# Sine_5KW_co_sac.net
KiCad netlist of a schematic drawn in EAGLE
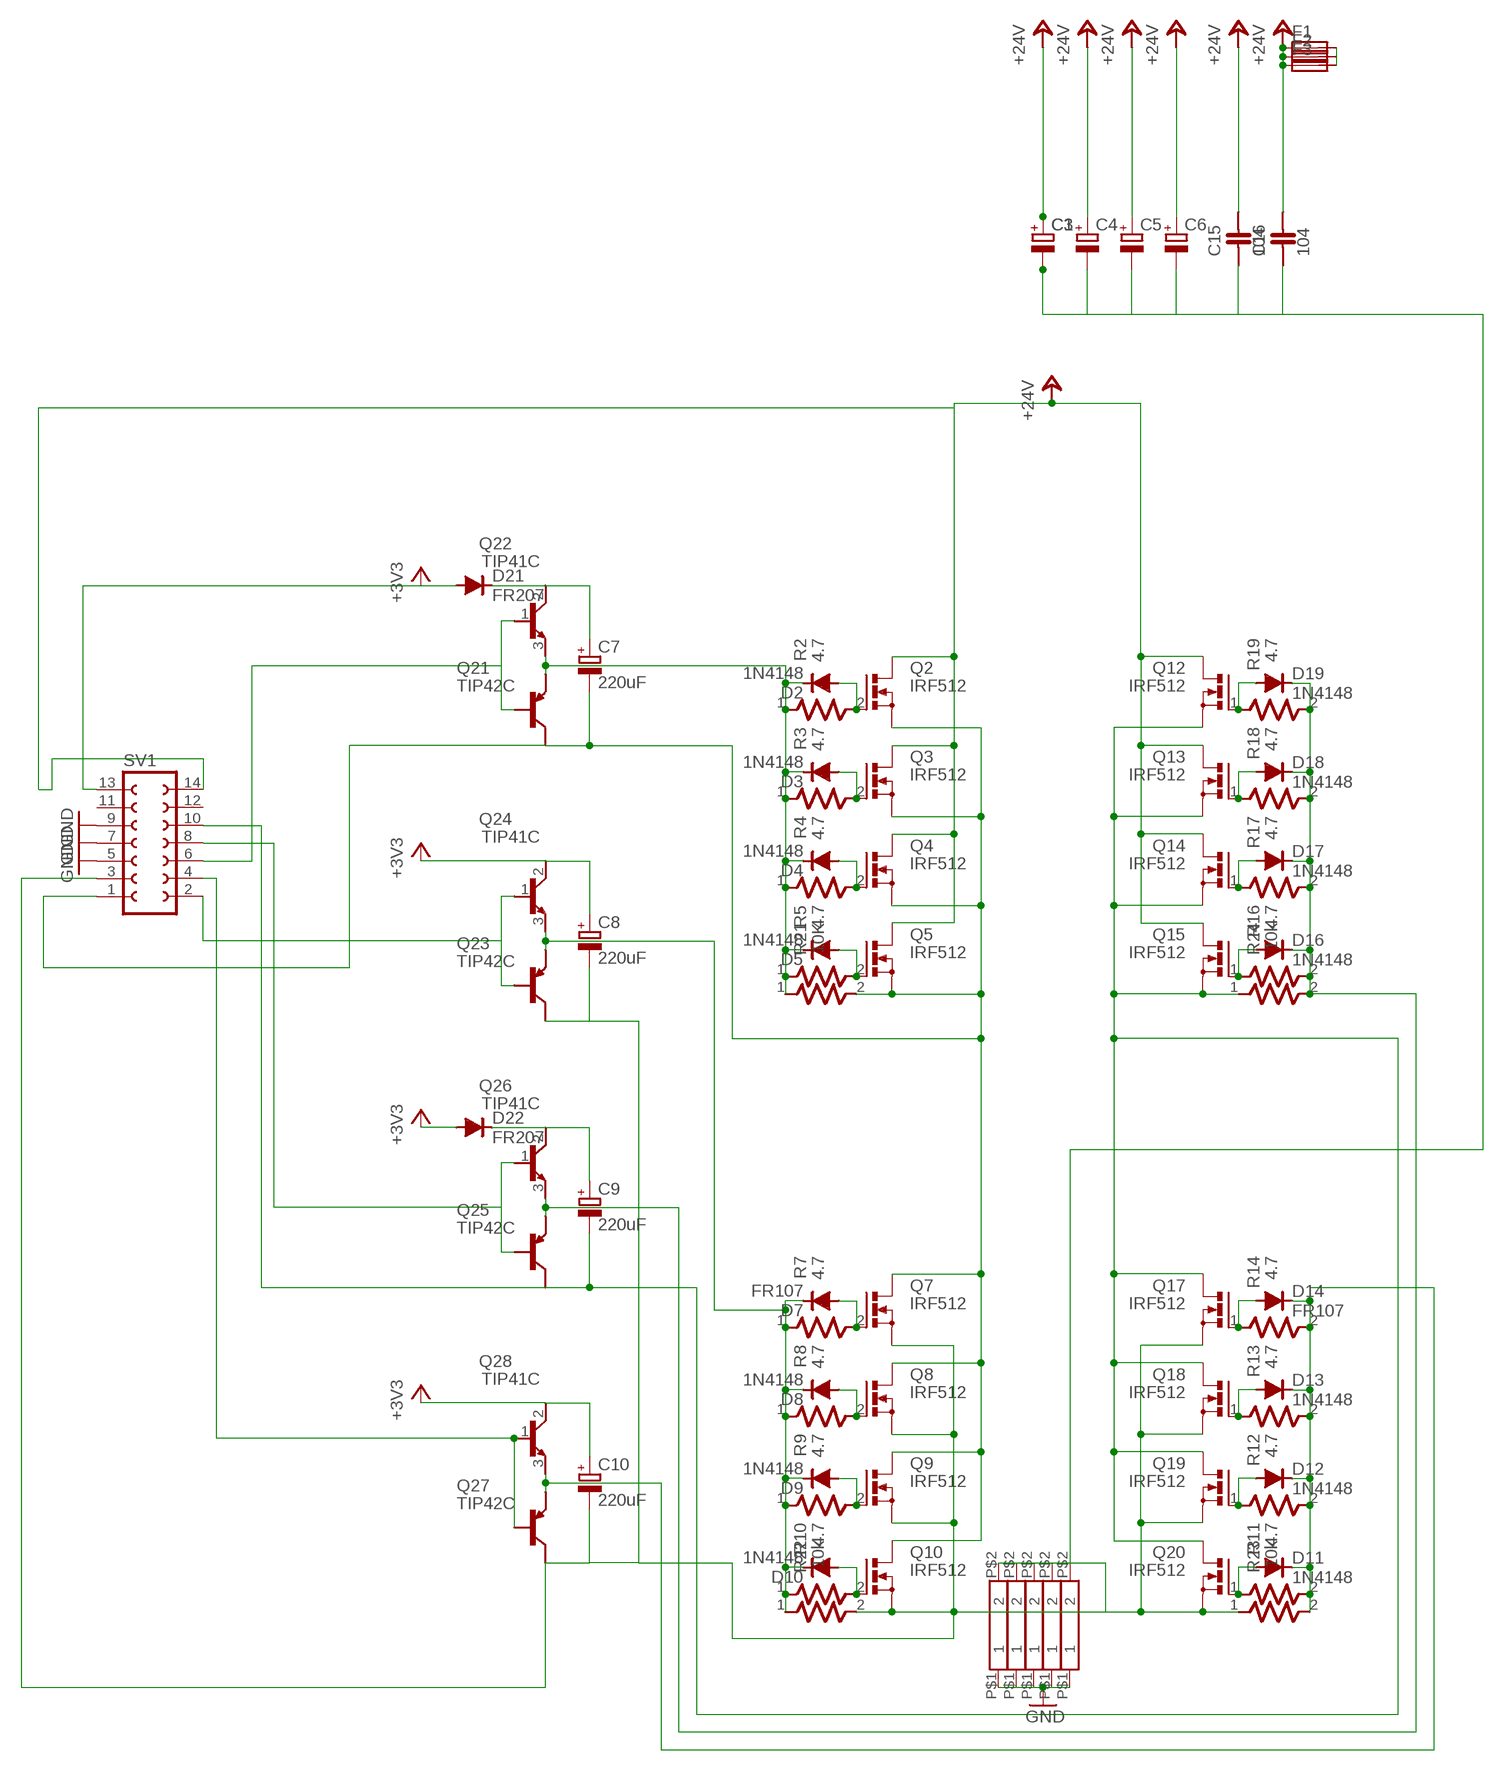
[diagram p0: schematic, sheet 1]

(export (version "E")
  (design (tool "Eeschema 10.0.6"))
  (components
    (comp (ref "C1")
      (value "CPOL-EUE7.5-18")
      (footprint "eagle-import:E7,5-18")
      (libsource (lib "eagle-import") (part "CPOL-EUE7.5-18"))
    )
    (comp (ref "C3")
      (value "CPOL-EUE7.5-18")
      (footprint "eagle-import:E7,5-18")
      (libsource (lib "eagle-import") (part "CPOL-EUE7.5-18"))
    )
    (comp (ref "C4")
      (value "CPOL-EUE7.5-18")
      (footprint "eagle-import:E7,5-18")
      (libsource (lib "eagle-import") (part "CPOL-EUE7.5-18"))
    )
    (comp (ref "C5")
      (value "CPOL-EUE7.5-18")
      (footprint "eagle-import:E7,5-18")
      (libsource (lib "eagle-import") (part "CPOL-EUE7.5-18"))
    )
    (comp (ref "C6")
      (value "CPOL-EUE7.5-18")
      (footprint "eagle-import:E7,5-18")
      (libsource (lib "eagle-import") (part "CPOL-EUE7.5-18"))
    )
    (comp (ref "C7")
      (value "220uF")
      (footprint "eagle-import:E5-8,5")
      (libsource (lib "eagle-import") (part "CPOL-EUE5-8.5"))
    )
    (comp (ref "C8")
      (value "220uF")
      (footprint "eagle-import:E5-8,5")
      (libsource (lib "eagle-import") (part "CPOL-EUE5-8.5"))
    )
    (comp (ref "C9")
      (value "220uF")
      (footprint "eagle-import:E5-8,5")
      (libsource (lib "eagle-import") (part "CPOL-EUE5-8.5"))
    )
    (comp (ref "C10")
      (value "220uF")
      (footprint "eagle-import:E5-8,5")
      (libsource (lib "eagle-import") (part "CPOL-EUE5-8.5"))
    )
    (comp (ref "C15")
      (value "104")
      (footprint "eagle-import:CAP-NP5")
      (libsource (lib "eagle-import") (part "CAP-NP5"))
    )
    (comp (ref "C16")
      (value "104")
      (footprint "eagle-import:CAP-NP5")
      (libsource (lib "eagle-import") (part "CAP-NP5"))
    )
    (comp (ref "D2")
      (value "1N4148")
      (footprint "eagle-import:D-7,5")
      (libsource (lib "eagle-import") (part "1N4148"))
    )
    (comp (ref "D3")
      (value "1N4148")
      (footprint "eagle-import:D-7,5")
      (libsource (lib "eagle-import") (part "1N4148"))
    )
    (comp (ref "D4")
      (value "1N4148")
      (footprint "eagle-import:D-7,5")
      (libsource (lib "eagle-import") (part "1N4148"))
    )
    (comp (ref "D5")
      (value "1N4148")
      (footprint "eagle-import:D-7,5")
      (libsource (lib "eagle-import") (part "1N4148"))
    )
    (comp (ref "D7")
      (value "FR107")
      (footprint "eagle-import:D-7,5")
      (libsource (lib "eagle-import") (part "1N4148"))
    )
    (comp (ref "D8")
      (value "1N4148")
      (footprint "eagle-import:D-7,5")
      (libsource (lib "eagle-import") (part "1N4148"))
    )
    (comp (ref "D9")
      (value "1N4148")
      (footprint "eagle-import:D-7,5")
      (libsource (lib "eagle-import") (part "1N4148"))
    )
    (comp (ref "D10")
      (value "1N4148")
      (footprint "eagle-import:D-7,5")
      (libsource (lib "eagle-import") (part "1N4148"))
    )
    (comp (ref "D11")
      (value "1N4148")
      (footprint "eagle-import:D-7,5")
      (libsource (lib "eagle-import") (part "1N4148"))
    )
    (comp (ref "D12")
      (value "1N4148")
      (footprint "eagle-import:D-7,5")
      (libsource (lib "eagle-import") (part "1N4148"))
    )
    (comp (ref "D13")
      (value "1N4148")
      (footprint "eagle-import:D-7,5")
      (libsource (lib "eagle-import") (part "1N4148"))
    )
    (comp (ref "D14")
      (value "FR107")
      (footprint "eagle-import:D-7,5")
      (libsource (lib "eagle-import") (part "1N4148"))
    )
    (comp (ref "D16")
      (value "1N4148")
      (footprint "eagle-import:D-7,5")
      (libsource (lib "eagle-import") (part "1N4148"))
    )
    (comp (ref "D17")
      (value "1N4148")
      (footprint "eagle-import:D-7,5")
      (libsource (lib "eagle-import") (part "1N4148"))
    )
    (comp (ref "D18")
      (value "1N4148")
      (footprint "eagle-import:D-7,5")
      (libsource (lib "eagle-import") (part "1N4148"))
    )
    (comp (ref "D19")
      (value "1N4148")
      (footprint "eagle-import:D-7,5")
      (libsource (lib "eagle-import") (part "1N4148"))
    )
    (comp (ref "D21")
      (value "FR207")
      (footprint "eagle-import:D-7,5")
      (libsource (lib "eagle-import") (part "1N4148"))
    )
    (comp (ref "D22")
      (value "FR207")
      (footprint "eagle-import:D-7,5")
      (libsource (lib "eagle-import") (part "1N4148"))
    )
    (comp (ref "F1")
      (value "LITTLEFUSE")
      (footprint "eagle-import:LITTLEFUSE")
      (libsource (lib "eagle-import") (part "LITTLEFUSE"))
    )
    (comp (ref "F2")
      (value "LITTLEFUSE")
      (footprint "eagle-import:LITTLEFUSE")
      (libsource (lib "eagle-import") (part "LITTLEFUSE"))
    )
    (comp (ref "F3")
      (value "LITTLEFUSE")
      (footprint "eagle-import:LITTLEFUSE")
      (libsource (lib "eagle-import") (part "LITTLEFUSE"))
    )
    (comp (ref "Q2")
      (value "IRF512")
      (footprint "eagle-import:TO220BV")
      (libsource (lib "eagle-import") (part "IRF512"))
    )
    (comp (ref "Q3")
      (value "IRF512")
      (footprint "eagle-import:TO220BV")
      (libsource (lib "eagle-import") (part "IRF512"))
    )
    (comp (ref "Q4")
      (value "IRF512")
      (footprint "eagle-import:TO220BV")
      (libsource (lib "eagle-import") (part "IRF512"))
    )
    (comp (ref "Q5")
      (value "IRF512")
      (footprint "eagle-import:TO220BV")
      (libsource (lib "eagle-import") (part "IRF512"))
    )
    (comp (ref "Q7")
      (value "IRF512")
      (footprint "eagle-import:TO220BV")
      (libsource (lib "eagle-import") (part "IRF512"))
    )
    (comp (ref "Q8")
      (value "IRF512")
      (footprint "eagle-import:TO220BV")
      (libsource (lib "eagle-import") (part "IRF512"))
    )
    (comp (ref "Q9")
      (value "IRF512")
      (footprint "eagle-import:TO220BV")
      (libsource (lib "eagle-import") (part "IRF512"))
    )
    (comp (ref "Q10")
      (value "IRF512")
      (footprint "eagle-import:TO220BV")
      (libsource (lib "eagle-import") (part "IRF512"))
    )
    (comp (ref "Q12")
      (value "IRF512")
      (footprint "eagle-import:TO220BV")
      (libsource (lib "eagle-import") (part "IRF512"))
    )
    (comp (ref "Q13")
      (value "IRF512")
      (footprint "eagle-import:TO220BV")
      (libsource (lib "eagle-import") (part "IRF512"))
    )
    (comp (ref "Q14")
      (value "IRF512")
      (footprint "eagle-import:TO220BV")
      (fields (field (name "SPICEPREFIX") "M"))
      (libsource (lib "eagle-import") (part "IRF512"))
    )
    (comp (ref "Q15")
      (value "IRF512")
      (footprint "eagle-import:TO220BV")
      (libsource (lib "eagle-import") (part "IRF512"))
    )
    (comp (ref "Q17")
      (value "IRF512")
      (footprint "eagle-import:TO220BV")
      (libsource (lib "eagle-import") (part "IRF512"))
    )
    (comp (ref "Q18")
      (value "IRF512")
      (footprint "eagle-import:TO220BV")
      (libsource (lib "eagle-import") (part "IRF512"))
    )
    (comp (ref "Q19")
      (value "IRF512")
      (footprint "eagle-import:TO220BV")
      (libsource (lib "eagle-import") (part "IRF512"))
    )
    (comp (ref "Q20")
      (value "IRF512")
      (footprint "eagle-import:TO220BV")
      (libsource (lib "eagle-import") (part "IRF512"))
    )
    (comp (ref "Q21")
      (value "TIP42C")
      (footprint "eagle-import:TIP-127")
      (libsource (lib "eagle-import") (part "TIP-127"))
    )
    (comp (ref "Q22")
      (value "TIP41C")
      (footprint "eagle-import:TIP-127")
      (libsource (lib "eagle-import") (part "TIP122"))
    )
    (comp (ref "Q23")
      (value "TIP42C")
      (footprint "eagle-import:TIP-127")
      (libsource (lib "eagle-import") (part "TIP-127"))
    )
    (comp (ref "Q24")
      (value "TIP41C")
      (footprint "eagle-import:TIP-127")
      (libsource (lib "eagle-import") (part "TIP122"))
    )
    (comp (ref "Q25")
      (value "TIP42C")
      (footprint "eagle-import:TIP-127")
      (libsource (lib "eagle-import") (part "TIP-127"))
    )
    (comp (ref "Q26")
      (value "TIP41C")
      (footprint "eagle-import:TIP-127")
      (libsource (lib "eagle-import") (part "TIP122"))
    )
    (comp (ref "Q27")
      (value "TIP42C")
      (footprint "eagle-import:TIP-127")
      (libsource (lib "eagle-import") (part "TIP-127"))
    )
    (comp (ref "Q28")
      (value "TIP41C")
      (footprint "eagle-import:TIP-127")
      (libsource (lib "eagle-import") (part "TIP122"))
    )
    (comp (ref "R2")
      (value "4.7")
      (footprint "eagle-import:R-7,5")
      (libsource (lib "eagle-import") (part "R-7,5"))
    )
    (comp (ref "R3")
      (value "4.7")
      (footprint "eagle-import:R-7,5")
      (libsource (lib "eagle-import") (part "R-7,5"))
    )
    (comp (ref "R4")
      (value "4.7")
      (footprint "eagle-import:R-7,5")
      (libsource (lib "eagle-import") (part "R-7,5"))
    )
    (comp (ref "R5")
      (value "4.7")
      (footprint "eagle-import:R-7,5")
      (libsource (lib "eagle-import") (part "R-7,5"))
    )
    (comp (ref "R7")
      (value "4.7")
      (footprint "eagle-import:R-7,5")
      (libsource (lib "eagle-import") (part "R-7,5"))
    )
    (comp (ref "R8")
      (value "4.7")
      (footprint "eagle-import:R-7,5")
      (libsource (lib "eagle-import") (part "R-7,5"))
    )
    (comp (ref "R9")
      (value "4.7")
      (footprint "eagle-import:R-7,5")
      (libsource (lib "eagle-import") (part "R-7,5"))
    )
    (comp (ref "R10")
      (value "4.7")
      (footprint "eagle-import:R-7,5")
      (libsource (lib "eagle-import") (part "R-7,5"))
    )
    (comp (ref "R11")
      (value "4.7")
      (footprint "eagle-import:R-7,5")
      (libsource (lib "eagle-import") (part "R-7,5"))
    )
    (comp (ref "R12")
      (value "4.7")
      (footprint "eagle-import:R-7,5")
      (libsource (lib "eagle-import") (part "R-7,5"))
    )
    (comp (ref "R13")
      (value "4.7")
      (footprint "eagle-import:R-7,5")
      (libsource (lib "eagle-import") (part "R-7,5"))
    )
    (comp (ref "R14")
      (value "4.7")
      (footprint "eagle-import:R-7,5")
      (libsource (lib "eagle-import") (part "R-7,5"))
    )
    (comp (ref "R16")
      (value "4.7")
      (footprint "eagle-import:R-7,5")
      (libsource (lib "eagle-import") (part "R-7,5"))
    )
    (comp (ref "R17")
      (value "4.7")
      (footprint "eagle-import:R-7,5")
      (libsource (lib "eagle-import") (part "R-7,5"))
    )
    (comp (ref "R18")
      (value "4.7")
      (footprint "eagle-import:R-7,5")
      (libsource (lib "eagle-import") (part "R-7,5"))
    )
    (comp (ref "R19")
      (value "4.7")
      (footprint "eagle-import:R-7,5")
      (libsource (lib "eagle-import") (part "R-7,5"))
    )
    (comp (ref "R21")
      (value "10K")
      (footprint "eagle-import:R-7,5")
      (libsource (lib "eagle-import") (part "R-7,5"))
    )
    (comp (ref "R22")
      (value "10k")
      (footprint "eagle-import:R-7,5")
      (libsource (lib "eagle-import") (part "R-7,5"))
    )
    (comp (ref "R23")
      (value "10k")
      (footprint "eagle-import:R-7,5")
      (libsource (lib "eagle-import") (part "R-7,5"))
    )
    (comp (ref "R24")
      (value "10k")
      (footprint "eagle-import:R-7,5")
      (libsource (lib "eagle-import") (part "R-7,5"))
    )
    (comp (ref "SV1")
      (value "FE07-2")
      (footprint "eagle-import:FE07-2")
      (fields (field (name "SPICEPREFIX") "X"))
      (libsource (lib "eagle-import") (part "FE07-2"))
    )
    (comp (ref "U$2")
      (value "SHUNT")
      (footprint "eagle-import:SHUNT")
      (libsource (lib "eagle-import") (part "SHUNT"))
    )
    (comp (ref "U$3")
      (value "SHUNT")
      (footprint "eagle-import:SHUNT")
      (libsource (lib "eagle-import") (part "SHUNT"))
    )
    (comp (ref "U$8")
      (value "SHUNT")
      (footprint "eagle-import:SHUNT")
      (libsource (lib "eagle-import") (part "SHUNT"))
    )
    (comp (ref "U$9")
      (value "SHUNT")
      (footprint "eagle-import:SHUNT")
      (libsource (lib "eagle-import") (part "SHUNT"))
    )
    (comp (ref "U$10")
      (value "SHUNT")
      (footprint "eagle-import:SHUNT")
      (libsource (lib "eagle-import") (part "SHUNT"))
    )
  )
  (nets
    (net (code "1") (name "+3V3") (class "Default")
      (node (ref "C10") (pin "+") (pinfunction "+_+") (pintype "passive"))
      (node (ref "C8") (pin "+") (pinfunction "+_+") (pintype "passive"))
      (node (ref "D21") (pin "A") (pinfunction "A_A") (pintype "passive"))
      (node (ref "D22") (pin "A") (pinfunction "A_A") (pintype "passive"))
      (node (ref "Q24") (pin "2") (pinfunction "C_2") (pintype "passive"))
      (node (ref "Q28") (pin "2") (pinfunction "C_2") (pintype "passive"))
      (node (ref "SV1") (pin "13") (pinfunction "13_13") (pintype "passive"))
    )
    (net (code "2") (name "+24V") (class "Default")
      (node (ref "C1") (pin "+") (pinfunction "+_+") (pintype "passive"))
      (node (ref "C15") (pin "2") (pinfunction "2_2") (pintype "passive"))
      (node (ref "C16") (pin "2") (pinfunction "2_2") (pintype "passive"))
      (node (ref "C3") (pin "+") (pinfunction "+_+") (pintype "passive"))
      (node (ref "C4") (pin "+") (pinfunction "+_+") (pintype "passive"))
      (node (ref "C5") (pin "+") (pinfunction "+_+") (pintype "passive"))
      (node (ref "C6") (pin "+") (pinfunction "+_+") (pintype "passive"))
      (node (ref "F1") (pin "1") (pinfunction "1_1") (pintype "passive"))
      (node (ref "F2") (pin "1") (pinfunction "1_1") (pintype "passive"))
      (node (ref "F3") (pin "1") (pinfunction "1_1") (pintype "passive"))
      (node (ref "Q12") (pin "D") (pinfunction "D_D") (pintype "passive"))
      (node (ref "Q13") (pin "D") (pinfunction "D_D") (pintype "passive"))
      (node (ref "Q14") (pin "D") (pinfunction "D_D") (pintype "passive"))
      (node (ref "Q15") (pin "D") (pinfunction "D_D") (pintype "passive"))
      (node (ref "Q2") (pin "D") (pinfunction "D_D") (pintype "passive"))
      (node (ref "Q3") (pin "D") (pinfunction "D_D") (pintype "passive"))
      (node (ref "Q4") (pin "D") (pinfunction "D_D") (pintype "passive"))
      (node (ref "Q5") (pin "D") (pinfunction "D_D") (pintype "passive"))
      (node (ref "SV1") (pin "14") (pinfunction "14_14") (pintype "passive"))
    )
    (net (code "3") (name "GND") (class "Default")
      (node (ref "SV1") (pin "5") (pinfunction "5_5") (pintype "passive"))
      (node (ref "SV1") (pin "7") (pinfunction "7_7") (pintype "passive"))
      (node (ref "SV1") (pin "9") (pinfunction "9_9") (pintype "passive"))
      (node (ref "U$10") (pin "P$1") (pinfunction "1_P$1") (pintype "bidirectional"))
      (node (ref "U$2") (pin "P$1") (pinfunction "1_P$1") (pintype "bidirectional"))
      (node (ref "U$3") (pin "P$1") (pinfunction "1_P$1") (pintype "bidirectional"))
      (node (ref "U$8") (pin "P$1") (pinfunction "1_P$1") (pintype "bidirectional"))
      (node (ref "U$9") (pin "P$1") (pinfunction "1_P$1") (pintype "bidirectional"))
    )
    (net (code "4") (name "Net-(D2-PadA)") (class "Default")
      (node (ref "D2") (pin "A") (pinfunction "A_A") (pintype "passive"))
      (node (ref "Q2") (pin "G") (pinfunction "G_G") (pintype "passive"))
      (node (ref "R2") (pin "2") (pinfunction "2_2") (pintype "passive"))
    )
    (net (code "5") (name "Net-(D3-PadA)") (class "Default")
      (node (ref "D3") (pin "A") (pinfunction "A_A") (pintype "passive"))
      (node (ref "Q3") (pin "G") (pinfunction "G_G") (pintype "passive"))
      (node (ref "R3") (pin "2") (pinfunction "2_2") (pintype "passive"))
    )
    (net (code "6") (name "Net-(D4-PadA)") (class "Default")
      (node (ref "D4") (pin "A") (pinfunction "A_A") (pintype "passive"))
      (node (ref "Q4") (pin "G") (pinfunction "G_G") (pintype "passive"))
      (node (ref "R4") (pin "2") (pinfunction "2_2") (pintype "passive"))
    )
    (net (code "7") (name "Net-(D5-PadA)") (class "Default")
      (node (ref "D5") (pin "A") (pinfunction "A_A") (pintype "passive"))
      (node (ref "Q5") (pin "G") (pinfunction "G_G") (pintype "passive"))
      (node (ref "R5") (pin "2") (pinfunction "2_2") (pintype "passive"))
    )
    (net (code "8") (name "Net-(D7-PadA)") (class "Default")
      (node (ref "D7") (pin "A") (pinfunction "A_A") (pintype "passive"))
      (node (ref "Q7") (pin "G") (pinfunction "G_G") (pintype "passive"))
      (node (ref "R7") (pin "2") (pinfunction "2_2") (pintype "passive"))
    )
    (net (code "9") (name "Net-(D8-PadA)") (class "Default")
      (node (ref "D8") (pin "A") (pinfunction "A_A") (pintype "passive"))
      (node (ref "Q8") (pin "G") (pinfunction "G_G") (pintype "passive"))
      (node (ref "R8") (pin "2") (pinfunction "2_2") (pintype "passive"))
    )
    (net (code "10") (name "Net-(D9-PadA)") (class "Default")
      (node (ref "D9") (pin "A") (pinfunction "A_A") (pintype "passive"))
      (node (ref "Q9") (pin "G") (pinfunction "G_G") (pintype "passive"))
      (node (ref "R9") (pin "2") (pinfunction "2_2") (pintype "passive"))
    )
    (net (code "11") (name "Net-(D10-PadA)") (class "Default")
      (node (ref "D10") (pin "A") (pinfunction "A_A") (pintype "passive"))
      (node (ref "Q10") (pin "G") (pinfunction "G_G") (pintype "passive"))
      (node (ref "R10") (pin "2") (pinfunction "2_2") (pintype "passive"))
    )
    (net (code "12") (name "Net-(D11-PadA)") (class "Default")
      (node (ref "D11") (pin "A") (pinfunction "A_A") (pintype "passive"))
      (node (ref "Q20") (pin "G") (pinfunction "G_G") (pintype "passive"))
      (node (ref "R11") (pin "1") (pinfunction "1_1") (pintype "passive"))
    )
    (net (code "13") (name "Net-(D12-PadA)") (class "Default")
      (node (ref "D12") (pin "A") (pinfunction "A_A") (pintype "passive"))
      (node (ref "Q19") (pin "G") (pinfunction "G_G") (pintype "passive"))
      (node (ref "R12") (pin "1") (pinfunction "1_1") (pintype "passive"))
    )
    (net (code "14") (name "Net-(D13-PadA)") (class "Default")
      (node (ref "D13") (pin "A") (pinfunction "A_A") (pintype "passive"))
      (node (ref "Q18") (pin "G") (pinfunction "G_G") (pintype "passive"))
      (node (ref "R13") (pin "1") (pinfunction "1_1") (pintype "passive"))
    )
    (net (code "15") (name "Net-(D14-PadA)") (class "Default")
      (node (ref "D14") (pin "A") (pinfunction "A_A") (pintype "passive"))
      (node (ref "Q17") (pin "G") (pinfunction "G_G") (pintype "passive"))
      (node (ref "R14") (pin "1") (pinfunction "1_1") (pintype "passive"))
    )
    (net (code "16") (name "Net-(D16-PadA)") (class "Default")
      (node (ref "D16") (pin "A") (pinfunction "A_A") (pintype "passive"))
      (node (ref "Q15") (pin "G") (pinfunction "G_G") (pintype "passive"))
      (node (ref "R16") (pin "1") (pinfunction "1_1") (pintype "passive"))
    )
    (net (code "17") (name "Net-(D17-PadA)") (class "Default")
      (node (ref "D17") (pin "A") (pinfunction "A_A") (pintype "passive"))
      (node (ref "Q14") (pin "G") (pinfunction "G_G") (pintype "passive"))
      (node (ref "R17") (pin "1") (pinfunction "1_1") (pintype "passive"))
    )
    (net (code "18") (name "Net-(D18-PadA)") (class "Default")
      (node (ref "D18") (pin "A") (pinfunction "A_A") (pintype "passive"))
      (node (ref "Q13") (pin "G") (pinfunction "G_G") (pintype "passive"))
      (node (ref "R18") (pin "1") (pinfunction "1_1") (pintype "passive"))
    )
    (net (code "19") (name "Net-(D19-PadA)") (class "Default")
      (node (ref "D19") (pin "A") (pinfunction "A_A") (pintype "passive"))
      (node (ref "Q12") (pin "G") (pinfunction "G_G") (pintype "passive"))
      (node (ref "R19") (pin "1") (pinfunction "1_1") (pintype "passive"))
    )
    (net (code "20") (name "Net-(F1-Pad2)") (class "Default")
      (node (ref "F1") (pin "2") (pinfunction "2_2") (pintype "passive"))
      (node (ref "F2") (pin "2") (pinfunction "2_2") (pintype "passive"))
      (node (ref "F3") (pin "2") (pinfunction "2_2") (pintype "passive"))
    )
    (net (code "21") (name "Net-(Q21-B)") (class "Default")
      (node (ref "Q21") (pin "1") (pinfunction "B_1") (pintype "passive"))
      (node (ref "Q22") (pin "1") (pinfunction "B_1") (pintype "passive"))
      (node (ref "SV1") (pin "6") (pinfunction "6_6") (pintype "passive"))
    )
    (net (code "22") (name "Net-(Q21-C)") (class "Default")
      (node (ref "C7") (pin "-") (pinfunction "-_-") (pintype "passive"))
      (node (ref "Q10") (pin "D") (pinfunction "D_D") (pintype "passive"))
      (node (ref "Q2") (pin "S") (pinfunction "S_S") (pintype "passive"))
      (node (ref "Q21") (pin "2") (pinfunction "C_2") (pintype "passive"))
      (node (ref "Q3") (pin "S") (pinfunction "S_S") (pintype "passive"))
      (node (ref "Q4") (pin "S") (pinfunction "S_S") (pintype "passive"))
      (node (ref "Q5") (pin "S") (pinfunction "S_S") (pintype "passive"))
      (node (ref "Q7") (pin "D") (pinfunction "D_D") (pintype "passive"))
      (node (ref "Q8") (pin "D") (pinfunction "D_D") (pintype "passive"))
      (node (ref "Q9") (pin "D") (pinfunction "D_D") (pintype "passive"))
      (node (ref "R21") (pin "2") (pinfunction "2_2") (pintype "passive"))
      (node (ref "SV1") (pin "1") (pinfunction "1_1") (pintype "passive"))
    )
    (net (code "23") (name "Net-(Q21-E)") (class "Default")
      (node (ref "D2") (pin "C") (pinfunction "C_C") (pintype "passive"))
      (node (ref "D3") (pin "C") (pinfunction "C_C") (pintype "passive"))
      (node (ref "D4") (pin "C") (pinfunction "C_C") (pintype "passive"))
      (node (ref "D5") (pin "C") (pinfunction "C_C") (pintype "passive"))
      (node (ref "Q21") (pin "3") (pinfunction "E_3") (pintype "passive"))
      (node (ref "Q22") (pin "3") (pinfunction "E_3") (pintype "passive"))
      (node (ref "R2") (pin "1") (pinfunction "1_1") (pintype "passive"))
      (node (ref "R21") (pin "1") (pinfunction "1_1") (pintype "passive"))
      (node (ref "R3") (pin "1") (pinfunction "1_1") (pintype "passive"))
      (node (ref "R4") (pin "1") (pinfunction "1_1") (pintype "passive"))
      (node (ref "R5") (pin "1") (pinfunction "1_1") (pintype "passive"))
    )
    (net (code "24") (name "Net-(Q22-C)") (class "Default")
      (node (ref "C7") (pin "+") (pinfunction "+_+") (pintype "passive"))
      (node (ref "D21") (pin "C") (pinfunction "C_C") (pintype "passive"))
      (node (ref "Q22") (pin "2") (pinfunction "C_2") (pintype "passive"))
    )
    (net (code "25") (name "Net-(Q23-B)") (class "Default")
      (node (ref "Q23") (pin "1") (pinfunction "B_1") (pintype "passive"))
      (node (ref "Q24") (pin "1") (pinfunction "B_1") (pintype "passive"))
      (node (ref "SV1") (pin "2") (pinfunction "2_2") (pintype "passive"))
    )
    (net (code "26") (name "Net-(Q23-C)") (class "Default")
      (node (ref "C1") (pin "-") (pinfunction "-_-") (pintype "passive"))
      (node (ref "C10") (pin "-") (pinfunction "-_-") (pintype "passive"))
      (node (ref "C15") (pin "1") (pinfunction "1_1") (pintype "passive"))
      (node (ref "C16") (pin "1") (pinfunction "1_1") (pintype "passive"))
      (node (ref "C3") (pin "-") (pinfunction "-_-") (pintype "passive"))
      (node (ref "C4") (pin "-") (pinfunction "-_-") (pintype "passive"))
      (node (ref "C5") (pin "-") (pinfunction "-_-") (pintype "passive"))
      (node (ref "C6") (pin "-") (pinfunction "-_-") (pintype "passive"))
      (node (ref "C8") (pin "-") (pinfunction "-_-") (pintype "passive"))
      (node (ref "Q10") (pin "S") (pinfunction "S_S") (pintype "passive"))
      (node (ref "Q17") (pin "S") (pinfunction "S_S") (pintype "passive"))
      (node (ref "Q18") (pin "S") (pinfunction "S_S") (pintype "passive"))
      (node (ref "Q19") (pin "S") (pinfunction "S_S") (pintype "passive"))
      (node (ref "Q20") (pin "S") (pinfunction "S_S") (pintype "passive"))
      (node (ref "Q23") (pin "2") (pinfunction "C_2") (pintype "passive"))
      (node (ref "Q27") (pin "2") (pinfunction "C_2") (pintype "passive"))
      (node (ref "Q7") (pin "S") (pinfunction "S_S") (pintype "passive"))
      (node (ref "Q8") (pin "S") (pinfunction "S_S") (pintype "passive"))
      (node (ref "Q9") (pin "S") (pinfunction "S_S") (pintype "passive"))
      (node (ref "R22") (pin "2") (pinfunction "2_2") (pintype "passive"))
      (node (ref "R23") (pin "1") (pinfunction "1_1") (pintype "passive"))
      (node (ref "SV1") (pin "3") (pinfunction "3_3") (pintype "passive"))
      (node (ref "U$10") (pin "P$2") (pinfunction "2_P$2") (pintype "bidirectional"))
      (node (ref "U$2") (pin "P$2") (pinfunction "2_P$2") (pintype "bidirectional"))
      (node (ref "U$3") (pin "P$2") (pinfunction "2_P$2") (pintype "bidirectional"))
      (node (ref "U$8") (pin "P$2") (pinfunction "2_P$2") (pintype "bidirectional"))
      (node (ref "U$9") (pin "P$2") (pinfunction "2_P$2") (pintype "bidirectional"))
    )
    (net (code "27") (name "Net-(Q23-E)") (class "Default")
      (node (ref "D10") (pin "C") (pinfunction "C_C") (pintype "passive"))
      (node (ref "D7") (pin "C") (pinfunction "C_C") (pintype "passive"))
      (node (ref "D8") (pin "C") (pinfunction "C_C") (pintype "passive"))
      (node (ref "D9") (pin "C") (pinfunction "C_C") (pintype "passive"))
      (node (ref "Q23") (pin "3") (pinfunction "E_3") (pintype "passive"))
      (node (ref "Q24") (pin "3") (pinfunction "E_3") (pintype "passive"))
      (node (ref "R10") (pin "1") (pinfunction "1_1") (pintype "passive"))
      (node (ref "R22") (pin "1") (pinfunction "1_1") (pintype "passive"))
      (node (ref "R7") (pin "1") (pinfunction "1_1") (pintype "passive"))
      (node (ref "R8") (pin "1") (pinfunction "1_1") (pintype "passive"))
      (node (ref "R9") (pin "1") (pinfunction "1_1") (pintype "passive"))
    )
    (net (code "28") (name "Net-(Q25-B)") (class "Default")
      (node (ref "Q25") (pin "1") (pinfunction "B_1") (pintype "passive"))
      (node (ref "Q26") (pin "1") (pinfunction "B_1") (pintype "passive"))
      (node (ref "SV1") (pin "8") (pinfunction "8_8") (pintype "passive"))
    )
    (net (code "29") (name "Net-(Q25-C)") (class "Default")
      (node (ref "C9") (pin "-") (pinfunction "-_-") (pintype "passive"))
      (node (ref "Q12") (pin "S") (pinfunction "S_S") (pintype "passive"))
      (node (ref "Q13") (pin "S") (pinfunction "S_S") (pintype "passive"))
      (node (ref "Q14") (pin "S") (pinfunction "S_S") (pintype "passive"))
      (node (ref "Q15") (pin "S") (pinfunction "S_S") (pintype "passive"))
      (node (ref "Q17") (pin "D") (pinfunction "D_D") (pintype "passive"))
      (node (ref "Q18") (pin "D") (pinfunction "D_D") (pintype "passive"))
      (node (ref "Q19") (pin "D") (pinfunction "D_D") (pintype "passive"))
      (node (ref "Q20") (pin "D") (pinfunction "D_D") (pintype "passive"))
      (node (ref "Q25") (pin "2") (pinfunction "C_2") (pintype "passive"))
      (node (ref "R24") (pin "1") (pinfunction "1_1") (pintype "passive"))
      (node (ref "SV1") (pin "10") (pinfunction "10_10") (pintype "passive"))
    )
    (net (code "30") (name "Net-(Q25-E)") (class "Default")
      (node (ref "D16") (pin "C") (pinfunction "C_C") (pintype "passive"))
      (node (ref "D17") (pin "C") (pinfunction "C_C") (pintype "passive"))
      (node (ref "D18") (pin "C") (pinfunction "C_C") (pintype "passive"))
      (node (ref "D19") (pin "C") (pinfunction "C_C") (pintype "passive"))
      (node (ref "Q25") (pin "3") (pinfunction "E_3") (pintype "passive"))
      (node (ref "Q26") (pin "3") (pinfunction "E_3") (pintype "passive"))
      (node (ref "R16") (pin "2") (pinfunction "2_2") (pintype "passive"))
      (node (ref "R17") (pin "2") (pinfunction "2_2") (pintype "passive"))
      (node (ref "R18") (pin "2") (pinfunction "2_2") (pintype "passive"))
      (node (ref "R19") (pin "2") (pinfunction "2_2") (pintype "passive"))
      (node (ref "R24") (pin "2") (pinfunction "2_2") (pintype "passive"))
    )
    (net (code "31") (name "Net-(Q26-C)") (class "Default")
      (node (ref "C9") (pin "+") (pinfunction "+_+") (pintype "passive"))
      (node (ref "D22") (pin "C") (pinfunction "C_C") (pintype "passive"))
      (node (ref "Q26") (pin "2") (pinfunction "C_2") (pintype "passive"))
    )
    (net (code "32") (name "Net-(Q27-B)") (class "Default")
      (node (ref "Q27") (pin "1") (pinfunction "B_1") (pintype "passive"))
      (node (ref "Q28") (pin "1") (pinfunction "B_1") (pintype "passive"))
      (node (ref "SV1") (pin "4") (pinfunction "4_4") (pintype "passive"))
    )
    (net (code "33") (name "Net-(Q27-E)") (class "Default")
      (node (ref "D11") (pin "C") (pinfunction "C_C") (pintype "passive"))
      (node (ref "D12") (pin "C") (pinfunction "C_C") (pintype "passive"))
      (node (ref "D13") (pin "C") (pinfunction "C_C") (pintype "passive"))
      (node (ref "D14") (pin "C") (pinfunction "C_C") (pintype "passive"))
      (node (ref "Q27") (pin "3") (pinfunction "E_3") (pintype "passive"))
      (node (ref "Q28") (pin "3") (pinfunction "E_3") (pintype "passive"))
      (node (ref "R11") (pin "2") (pinfunction "2_2") (pintype "passive"))
      (node (ref "R12") (pin "2") (pinfunction "2_2") (pintype "passive"))
      (node (ref "R13") (pin "2") (pinfunction "2_2") (pintype "passive"))
      (node (ref "R14") (pin "2") (pinfunction "2_2") (pintype "passive"))
      (node (ref "R23") (pin "2") (pinfunction "2_2") (pintype "passive"))
    )
    (net (code "34") (name "unconnected-(SV1-Pad11)") (class "Default")
      (node (ref "SV1") (pin "11") (pinfunction "11_11") (pintype "passive"))
    )
    (net (code "35") (name "unconnected-(SV1-Pad12)") (class "Default")
      (node (ref "SV1") (pin "12") (pinfunction "12_12") (pintype "passive"))
    )
  )
)
